# sensors.net
KiCad netlist of a schematic drawn in EAGLE
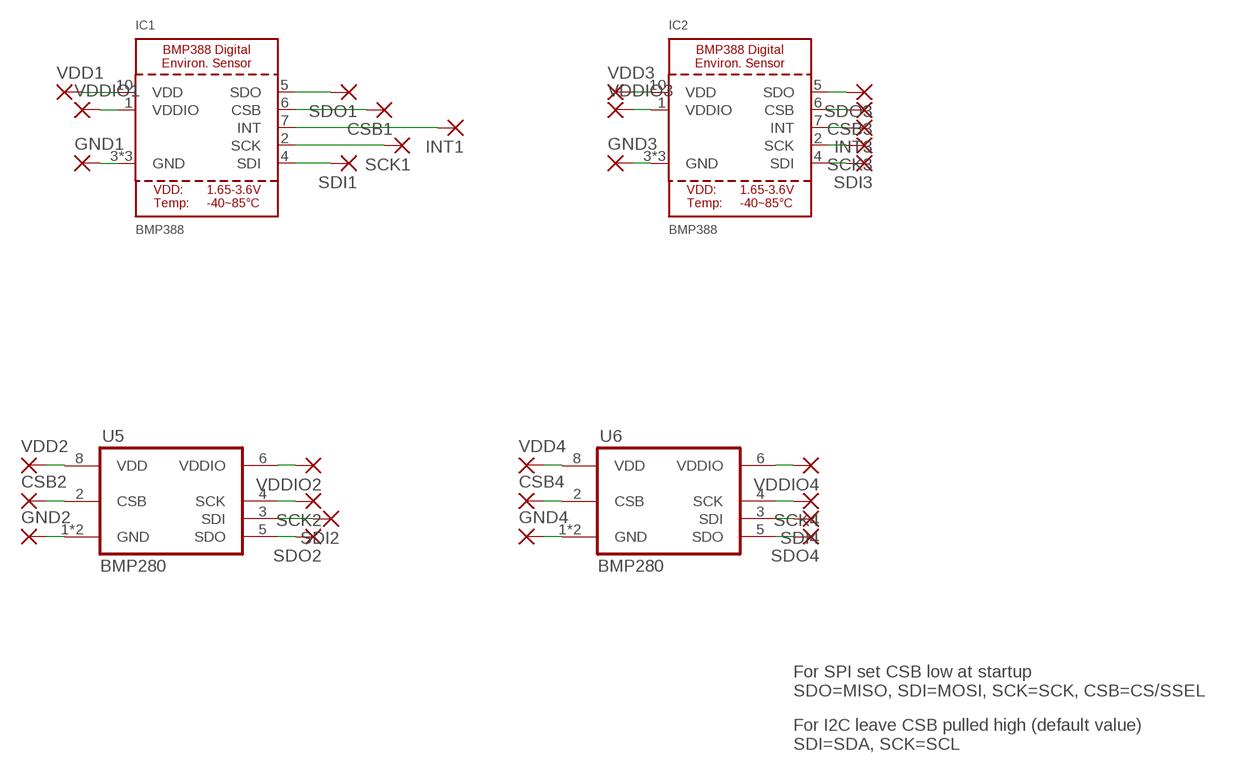
[diagram p0: schematic, sheet 1]

(export (version "E")
  (design (tool "Eeschema 10.0.6"))
  (components
    (comp (ref "CSB1")
      (value "SMD5")
      (footprint "eagle-import:SMD2,54-5,08")
      (libsource (lib "eagle-import") (part "SMD5"))
    )
    (comp (ref "CSB2")
      (value "SMD5")
      (footprint "eagle-import:SMD2,54-5,08")
      (libsource (lib "eagle-import") (part "SMD5"))
    )
    (comp (ref "CSB3")
      (value "SMD5")
      (footprint "eagle-import:SMD2,54-5,08")
      (libsource (lib "eagle-import") (part "SMD5"))
    )
    (comp (ref "CSB4")
      (value "SMD5")
      (footprint "eagle-import:SMD2,54-5,08")
      (libsource (lib "eagle-import") (part "SMD5"))
    )
    (comp (ref "GND1")
      (value "SMD5")
      (footprint "eagle-import:SMD2,54-5,08")
      (libsource (lib "eagle-import") (part "SMD5"))
    )
    (comp (ref "GND2")
      (value "SMD5")
      (footprint "eagle-import:SMD2,54-5,08")
      (libsource (lib "eagle-import") (part "SMD5"))
    )
    (comp (ref "GND3")
      (value "SMD5")
      (footprint "eagle-import:SMD2,54-5,08")
      (libsource (lib "eagle-import") (part "SMD5"))
    )
    (comp (ref "GND4")
      (value "SMD5")
      (footprint "eagle-import:SMD2,54-5,08")
      (libsource (lib "eagle-import") (part "SMD5"))
    )
    (comp (ref "IC1")
      (value "BMP388")
      (footprint "eagle-import:BMP388")
      (libsource (lib "eagle-import") (part "BMP388"))
    )
    (comp (ref "IC2")
      (value "BMP388")
      (footprint "eagle-import:BMP388")
      (libsource (lib "eagle-import") (part "BMP388"))
    )
    (comp (ref "INT1")
      (value "SMD5")
      (footprint "eagle-import:SMD2,54-5,08")
      (libsource (lib "eagle-import") (part "SMD5"))
    )
    (comp (ref "INT3")
      (value "SMD5")
      (footprint "eagle-import:SMD2,54-5,08")
      (libsource (lib "eagle-import") (part "SMD5"))
    )
    (comp (ref "SCK1")
      (value "SMD5")
      (footprint "eagle-import:SMD2,54-5,08")
      (libsource (lib "eagle-import") (part "SMD5"))
    )
    (comp (ref "SCK2")
      (value "SMD5")
      (footprint "eagle-import:SMD2,54-5,08")
      (libsource (lib "eagle-import") (part "SMD5"))
    )
    (comp (ref "SCK3")
      (value "SMD5")
      (footprint "eagle-import:SMD2,54-5,08")
      (libsource (lib "eagle-import") (part "SMD5"))
    )
    (comp (ref "SCK4")
      (value "SMD5")
      (footprint "eagle-import:SMD2,54-5,08")
      (libsource (lib "eagle-import") (part "SMD5"))
    )
    (comp (ref "SDI1")
      (value "SMD5")
      (footprint "eagle-import:SMD2,54-5,08")
      (libsource (lib "eagle-import") (part "SMD5"))
    )
    (comp (ref "SDI2")
      (value "SMD5")
      (footprint "eagle-import:SMD2,54-5,08")
      (libsource (lib "eagle-import") (part "SMD5"))
    )
    (comp (ref "SDI3")
      (value "SMD5")
      (footprint "eagle-import:SMD2,54-5,08")
      (libsource (lib "eagle-import") (part "SMD5"))
    )
    (comp (ref "SDI4")
      (value "SMD5")
      (footprint "eagle-import:SMD2,54-5,08")
      (libsource (lib "eagle-import") (part "SMD5"))
    )
    (comp (ref "SDO1")
      (value "SMD5")
      (footprint "eagle-import:SMD2,54-5,08")
      (libsource (lib "eagle-import") (part "SMD5"))
    )
    (comp (ref "SDO2")
      (value "SMD5")
      (footprint "eagle-import:SMD2,54-5,08")
      (libsource (lib "eagle-import") (part "SMD5"))
    )
    (comp (ref "SDO3")
      (value "SMD5")
      (footprint "eagle-import:SMD2,54-5,08")
      (libsource (lib "eagle-import") (part "SMD5"))
    )
    (comp (ref "SDO4")
      (value "SMD5")
      (footprint "eagle-import:SMD2,54-5,08")
      (libsource (lib "eagle-import") (part "SMD5"))
    )
    (comp (ref "U5")
      (value "BMP280")
      (footprint "eagle-import:BMP280")
      (libsource (lib "eagle-import") (part "BMP280"))
    )
    (comp (ref "U6")
      (value "BMP280")
      (footprint "eagle-import:BMP280")
      (libsource (lib "eagle-import") (part "BMP280"))
    )
    (comp (ref "VDD1")
      (value "SMD5")
      (footprint "eagle-import:SMD2,54-5,08")
      (libsource (lib "eagle-import") (part "SMD5"))
    )
    (comp (ref "VDD2")
      (value "SMD5")
      (footprint "eagle-import:SMD2,54-5,08")
      (libsource (lib "eagle-import") (part "SMD5"))
    )
    (comp (ref "VDD3")
      (value "SMD5")
      (footprint "eagle-import:SMD2,54-5,08")
      (libsource (lib "eagle-import") (part "SMD5"))
    )
    (comp (ref "VDD4")
      (value "SMD5")
      (footprint "eagle-import:SMD2,54-5,08")
      (libsource (lib "eagle-import") (part "SMD5"))
    )
    (comp (ref "VDDIO1")
      (value "SMD5")
      (footprint "eagle-import:SMD2,54-5,08")
      (libsource (lib "eagle-import") (part "SMD5"))
    )
    (comp (ref "VDDIO2")
      (value "SMD5")
      (footprint "eagle-import:SMD2,54-5,08")
      (libsource (lib "eagle-import") (part "SMD5"))
    )
    (comp (ref "VDDIO3")
      (value "SMD5")
      (footprint "eagle-import:SMD2,54-5,08")
      (libsource (lib "eagle-import") (part "SMD5"))
    )
    (comp (ref "VDDIO4")
      (value "SMD5")
      (footprint "eagle-import:SMD2,54-5,08")
      (libsource (lib "eagle-import") (part "SMD5"))
    )
  )
  (nets
    (net (code "1") (name "Net-(CSB1-P)") (class "Default")
      (node (ref "CSB1") (pin "1") (pinfunction "P_1") (pintype "passive"))
      (node (ref "IC1") (pin "6") (pinfunction "CSB_6") (pintype "input"))
    )
    (net (code "2") (name "Net-(CSB2-P)") (class "Default")
      (node (ref "CSB2") (pin "1") (pinfunction "P_1") (pintype "passive"))
      (node (ref "U5") (pin "2") (pinfunction "CSB_2") (pintype "input"))
    )
    (net (code "3") (name "Net-(CSB3-P)") (class "Default")
      (node (ref "CSB3") (pin "1") (pinfunction "P_1") (pintype "passive"))
      (node (ref "IC2") (pin "6") (pinfunction "CSB_6") (pintype "input"))
    )
    (net (code "4") (name "Net-(CSB4-P)") (class "Default")
      (node (ref "CSB4") (pin "1") (pinfunction "P_1") (pintype "passive"))
      (node (ref "U6") (pin "2") (pinfunction "CSB_2") (pintype "input"))
    )
    (net (code "5") (name "Net-(GND1-P)") (class "Default")
      (node (ref "GND1") (pin "1") (pinfunction "P_1") (pintype "passive"))
      (node (ref "IC1") (pin "3") (pinfunction "GND_3") (pintype "power_in"))
      (node (ref "IC1") (pin "8") (pinfunction "GND_8") (pintype "power_in"))
      (node (ref "IC1") (pin "9") (pinfunction "GND_9") (pintype "power_in"))
    )
    (net (code "6") (name "Net-(GND2-P)") (class "Default")
      (node (ref "GND2") (pin "1") (pinfunction "P_1") (pintype "passive"))
      (node (ref "U5") (pin "1") (pinfunction "GND_1") (pintype "power_in"))
      (node (ref "U5") (pin "7") (pinfunction "GND_7") (pintype "power_in"))
    )
    (net (code "7") (name "Net-(GND3-P)") (class "Default")
      (node (ref "GND3") (pin "1") (pinfunction "P_1") (pintype "passive"))
      (node (ref "IC2") (pin "3") (pinfunction "GND_3") (pintype "power_in"))
      (node (ref "IC2") (pin "8") (pinfunction "GND_8") (pintype "power_in"))
      (node (ref "IC2") (pin "9") (pinfunction "GND_9") (pintype "power_in"))
    )
    (net (code "8") (name "Net-(GND4-P)") (class "Default")
      (node (ref "GND4") (pin "1") (pinfunction "P_1") (pintype "passive"))
      (node (ref "U6") (pin "1") (pinfunction "GND_1") (pintype "power_in"))
      (node (ref "U6") (pin "7") (pinfunction "GND_7") (pintype "power_in"))
    )
    (net (code "9") (name "Net-(IC1-INT)") (class "Default")
      (node (ref "IC1") (pin "7") (pinfunction "INT_7") (pintype "output"))
      (node (ref "INT1") (pin "1") (pinfunction "P_1") (pintype "passive"))
    )
    (net (code "10") (name "Net-(IC1-SCK)") (class "Default")
      (node (ref "IC1") (pin "2") (pinfunction "SCK_2") (pintype "input"))
      (node (ref "SCK1") (pin "1") (pinfunction "P_1") (pintype "passive"))
    )
    (net (code "11") (name "Net-(IC1-SDI)") (class "Default")
      (node (ref "IC1") (pin "4") (pinfunction "SDI_4") (pintype "input"))
      (node (ref "SDI1") (pin "1") (pinfunction "P_1") (pintype "passive"))
    )
    (net (code "12") (name "Net-(IC1-SDO)") (class "Default")
      (node (ref "IC1") (pin "5") (pinfunction "SDO_5") (pintype "output"))
      (node (ref "SDO1") (pin "1") (pinfunction "P_1") (pintype "passive"))
    )
    (net (code "13") (name "Net-(IC1-VDD)") (class "Default")
      (node (ref "IC1") (pin "10") (pinfunction "VDD_10") (pintype "power_in"))
      (node (ref "VDD1") (pin "1") (pinfunction "P_1") (pintype "passive"))
    )
    (net (code "14") (name "Net-(IC1-VDDIO)") (class "Default")
      (node (ref "IC1") (pin "1") (pinfunction "VDDIO_1") (pintype "power_in"))
      (node (ref "VDDIO1") (pin "1") (pinfunction "P_1") (pintype "passive"))
    )
    (net (code "15") (name "Net-(IC2-INT)") (class "Default")
      (node (ref "IC2") (pin "7") (pinfunction "INT_7") (pintype "output"))
      (node (ref "INT3") (pin "1") (pinfunction "P_1") (pintype "passive"))
    )
    (net (code "16") (name "Net-(IC2-SCK)") (class "Default")
      (node (ref "IC2") (pin "2") (pinfunction "SCK_2") (pintype "input"))
      (node (ref "SCK3") (pin "1") (pinfunction "P_1") (pintype "passive"))
    )
    (net (code "17") (name "Net-(IC2-SDI)") (class "Default")
      (node (ref "IC2") (pin "4") (pinfunction "SDI_4") (pintype "input"))
      (node (ref "SDI3") (pin "1") (pinfunction "P_1") (pintype "passive"))
    )
    (net (code "18") (name "Net-(IC2-SDO)") (class "Default")
      (node (ref "IC2") (pin "5") (pinfunction "SDO_5") (pintype "output"))
      (node (ref "SDO3") (pin "1") (pinfunction "P_1") (pintype "passive"))
    )
    (net (code "19") (name "Net-(IC2-VDD)") (class "Default")
      (node (ref "IC2") (pin "10") (pinfunction "VDD_10") (pintype "power_in"))
      (node (ref "VDD3") (pin "1") (pinfunction "P_1") (pintype "passive"))
    )
    (net (code "20") (name "Net-(IC2-VDDIO)") (class "Default")
      (node (ref "IC2") (pin "1") (pinfunction "VDDIO_1") (pintype "power_in"))
      (node (ref "VDDIO3") (pin "1") (pinfunction "P_1") (pintype "passive"))
    )
    (net (code "21") (name "Net-(SCK2-P)") (class "Default")
      (node (ref "SCK2") (pin "1") (pinfunction "P_1") (pintype "passive"))
      (node (ref "U5") (pin "4") (pinfunction "SCK_4") (pintype "bidirectional"))
    )
    (net (code "22") (name "Net-(SCK4-P)") (class "Default")
      (node (ref "SCK4") (pin "1") (pinfunction "P_1") (pintype "passive"))
      (node (ref "U6") (pin "4") (pinfunction "SCK_4") (pintype "bidirectional"))
    )
    (net (code "23") (name "Net-(SDI2-P)") (class "Default")
      (node (ref "SDI2") (pin "1") (pinfunction "P_1") (pintype "passive"))
      (node (ref "U5") (pin "3") (pinfunction "SDI_3") (pintype "bidirectional"))
    )
    (net (code "24") (name "Net-(SDI4-P)") (class "Default")
      (node (ref "SDI4") (pin "1") (pinfunction "P_1") (pintype "passive"))
      (node (ref "U6") (pin "3") (pinfunction "SDI_3") (pintype "bidirectional"))
    )
    (net (code "25") (name "Net-(SDO2-P)") (class "Default")
      (node (ref "SDO2") (pin "1") (pinfunction "P_1") (pintype "passive"))
      (node (ref "U5") (pin "5") (pinfunction "SDO_5") (pintype "input"))
    )
    (net (code "26") (name "Net-(SDO4-P)") (class "Default")
      (node (ref "SDO4") (pin "1") (pinfunction "P_1") (pintype "passive"))
      (node (ref "U6") (pin "5") (pinfunction "SDO_5") (pintype "input"))
    )
    (net (code "27") (name "Net-(U5-VDD)") (class "Default")
      (node (ref "U5") (pin "8") (pinfunction "VDD_8") (pintype "power_in"))
      (node (ref "VDD2") (pin "1") (pinfunction "P_1") (pintype "passive"))
    )
    (net (code "28") (name "Net-(U5-VDDIO)") (class "Default")
      (node (ref "U5") (pin "6") (pinfunction "VDDIO_6") (pintype "power_in"))
      (node (ref "VDDIO2") (pin "1") (pinfunction "P_1") (pintype "passive"))
    )
    (net (code "29") (name "Net-(U6-VDD)") (class "Default")
      (node (ref "U6") (pin "8") (pinfunction "VDD_8") (pintype "power_in"))
      (node (ref "VDD4") (pin "1") (pinfunction "P_1") (pintype "passive"))
    )
    (net (code "30") (name "Net-(U6-VDDIO)") (class "Default")
      (node (ref "U6") (pin "6") (pinfunction "VDDIO_6") (pintype "power_in"))
      (node (ref "VDDIO4") (pin "1") (pinfunction "P_1") (pintype "passive"))
    )
  )
)
